# Pi5_Power.net
KiCad netlist of a schematic drawn in Altium Designer
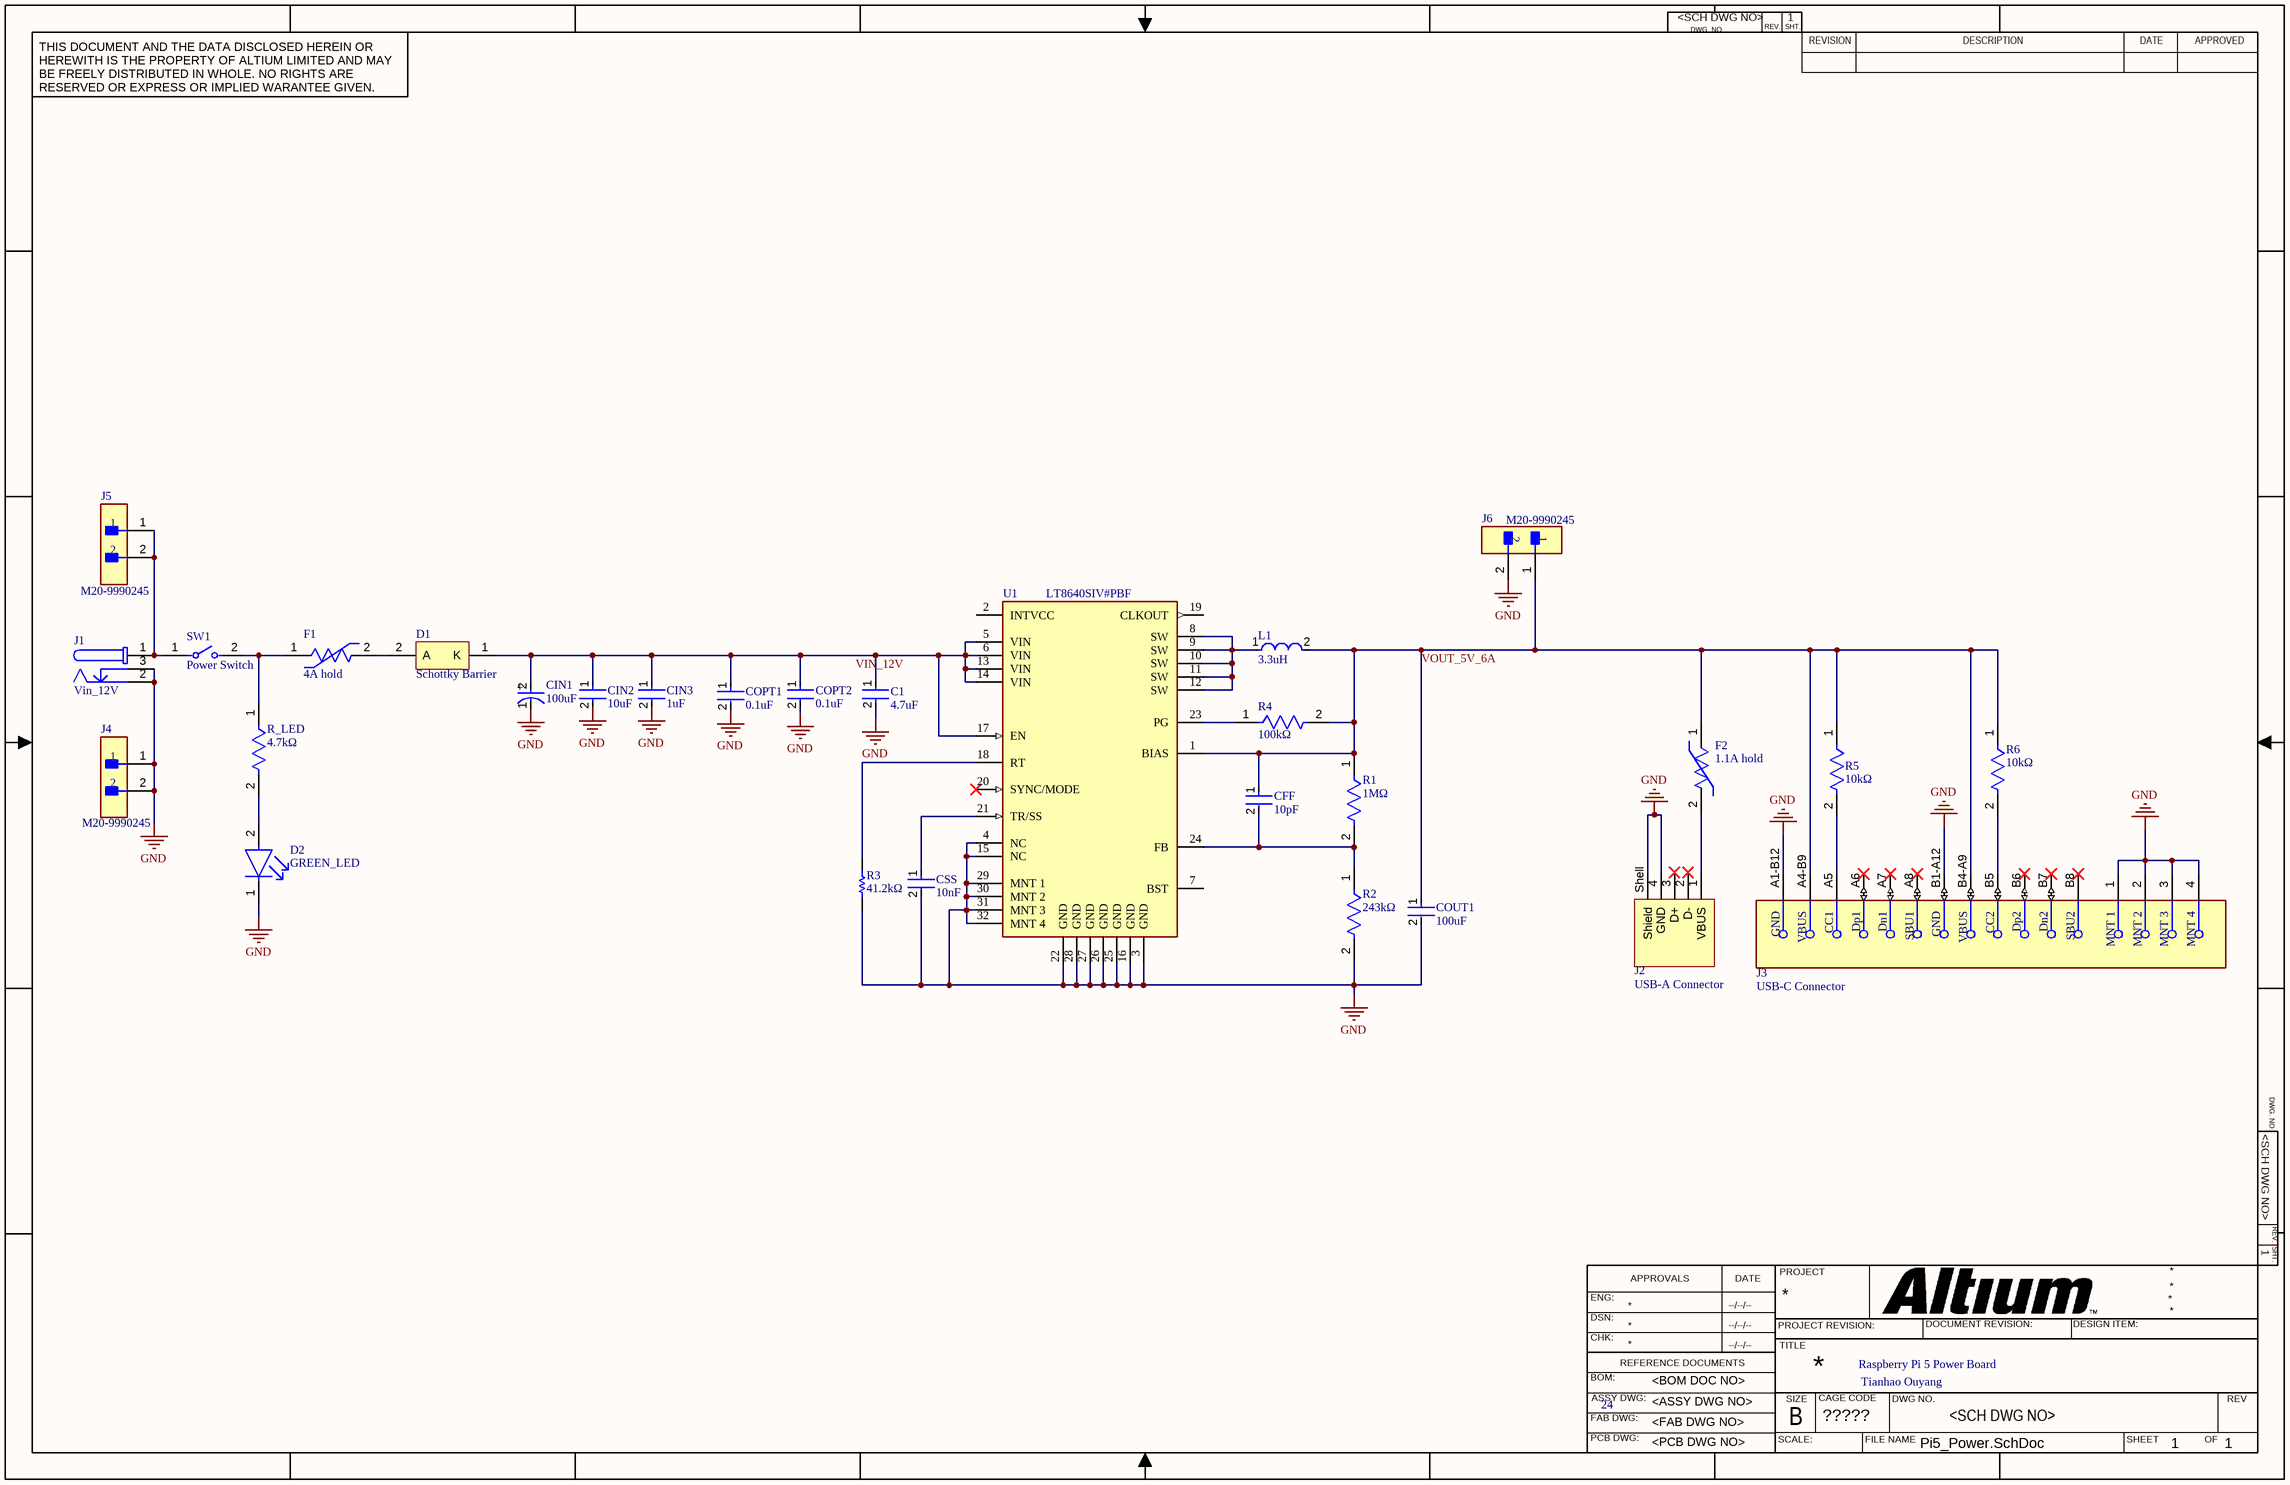
[diagram p0: Pi5_Power.SchDoc]

(export (version "E")
  (design (tool "Eeschema 10.0.6"))
  (components
    (comp (ref "C1")
      (value "4.7uF")
      (footprint "FP-GCM32E-0_3-IPC_B")
      (description "Ceramic Capacitor for Automotive 4.7uF ±10% 50VDC X7R 1210 Embossed T/R")
      (fields (field (name "VOLTAGE") "50V") (field (name "TOLERANCE") "20%"))
      (libsource (lib "Altium Content Vault") (part "f23184f103b6ebe33a8c269c53dcba6"))
    )
    (comp (ref "CFF")
      (value "10pF")
      (footprint "FP-C0805C-DN-MFG")
      (description "C0805 10 pF C0G 30ppm/°C 5.00% 250 V")
      (fields (field (name "TOLERANCE") "0.05") (field (name "MANUFACTURER PART NUMBER") "C0805C100JAGACTU"))
      (libsource (lib "Altium Content Vault") (part "b4654b650e69147ec39a6b967a45e02"))
    )
    (comp (ref "CIN1")
      (value "100uF")
      (footprint "FP-RAD-TH-D_6_3_0_5-L_11-MFG")
      (description "Aluminum Electrolytic Capacitors (Radial Lead Type) 100uF ±20% 25V")
      (fields (field (name "TOLERANCE") "20%"))
      (libsource (lib "Altium Content Vault") (part "a00bbbee19879c290e62620ae7e47b1"))
    )
    (comp (ref "CIN2")
      (value "10uF")
      (footprint "FP-GRM32-MFG")
      (description "CAP CER 10UF 50V X7R 1210")
      (fields (field (name "TOLERANCE") "10%") (field (name "MANUFACTURER PART NUMBER") "GRM32ER71H106KA12L"))
      (libsource (lib "Altium Content Vault") (part "11868f565c42a9108669ba33697ecf6"))
    )
    (comp (ref "CIN3")
      (value "1uF")
      (footprint "FP-C3216-160-0_2-IPC_B")
      (description "Multilayer Ceramic Capacitors 1uF ±10% 50V X7R SMD 1206")
      (fields (field (name "VOLTAGE") "25V") (field (name "TOLERANCE") "10%"))
      (libsource (lib "Altium Content Vault") (part "11868f565c42a9108669ba33697ecf6"))
    )
    (comp (ref "COPT1")
      (value "0.1uF")
      (footprint "FP-C1206C-EB-MFG")
      (description "CAP CER 0.1UF 250V X7R 1206")
      (fields
        (field (name "MANUFACTURER PART NUMBER") "C1206C104JARACTU")
        (field (name "OCTOPART") "https://octopart.com/c1206c104jaractu-kemet-16430893")
      )
      (libsource (lib "Altium Content Vault") (part "b4654b650e69147ec39a6b967a45e02"))
    )
    (comp (ref "COPT2")
      (value "0.1uF")
      (footprint "FP-C1206C-EB-MFG")
      (description "CAP CER 0.1UF 250V X7R 1206")
      (fields
        (field (name "MANUFACTURER PART NUMBER") "C1206C104JARACTU")
        (field (name "OCTOPART") "https://octopart.com/c1206c104jaractu-kemet-16430893")
      )
      (libsource (lib "Altium Content Vault") (part "b4654b650e69147ec39a6b967a45e02"))
    )
    (comp (ref "COUT1")
      (value "100uF")
      (footprint "FP-GRM32E-0_3-0_2-IPC_B")
      (description "Chip Multilayer Ceramic Capacitors for General Purpose, 1210, 100uF, X5R, 15%, 20%, 10V")
      (fields (field (name "TOLERANCE") "20%"))
      (libsource (lib "Altium Content Vault") (part "02cd4be3c70576c341d710602a673aa"))
    )
    (comp (ref "CSS")
      (value "10nF")
      (footprint "FP-C0603C-CF-MFG")
      (description "C0603 10,000 pF X7R 30ppm/°C 10.00% 25 V")
      (fields (field (name "TOLERANCE") "0.1") (field (name "MANUFACTURER PART NUMBER") "C0603C103K3RAC7411"))
      (libsource (lib "Altium Content Vault") (part "b4654b650e69147ec39a6b967a45e02"))
    )
    (comp (ref "D1")
      (value "Schottky Barrier")
      (footprint "ONSC-SMC-2-403-03_V")
      (description "Schottky Power Rectifier, 2-Pin SMC, Pb-Free, Tape and Reel")
      (fields (field (name "MANUFACTURER") "On Semiconductor") (field (name "PARTNUMBER") "MBRS540T3G"))
      (libsource (lib "Altium Content Vault") (part "ONSC-D-K1A2-2_A"))
    )
    (comp (ref "D2")
      (value "GREEN_LED")
      (footprint "FP-APHD1608LZGCK-MFG")
      (description "LED GREEN CLEAR 1608 SMD")
      (libsource (lib "Altium Content Vault") (part "8706943c75ba83719d021d2fdc84c58"))
    )
    (comp (ref "F1")
      (value "4A hold")
      (footprint "FP-2920L400-15MR-MFG")
      (description "PTC RESET FUSE 15V 4A 2920")
      (libsource (lib "Altium Content Vault") (part "fc31388045fc42ab786d6d00b506e9f"))
    )
    (comp (ref "F2")
      (value "1.1A hold")
      (footprint "FP-NANOSMDC110F-2-MFG")
      (description "PTC RESET FUSE 6V 1.1A 1206")
      (fields
        (field (name "MANUFACTURER") "Littelfuse")
        (field (name "OCTOPART") "https://octopart.com/nanosmdc110f-2-littelfuse-74215055")
      )
      (libsource (lib "Altium Content Vault") (part "fdf083d5f6389a9a1c4e51137f46658"))
    )
    (comp (ref "J1")
      (value "Vin_12V")
      (footprint "694108301002")
      (description "DC Power Jack Connector WR-DC, Male, Right Angled, THT, 5 A, 24 V")
      (libsource (lib "Altium Content Vault") (part "DC Power Jack"))
    )
    (comp (ref "J2")
      (value "USB-A Connector")
      (footprint "62900416021")
      (description "Wr-com; Right Angle Version 2.0; Connector SMT Socket, 30 V AC, 1.5A, 62900")
      (libsource (lib "Altium Content Vault") (part "USB 2.0_Type A_Receptacle_1 Port"))
    )
    (comp (ref "J3")
      (value "USB-C Connector")
      (footprint "FP-USB4105-GF-A-MFG")
      (description "CONN RCPT USB2.0 TYPEC 5A")
      (fields (field (name "MANUFACTURER PART NUMBER") "USB4105-GF-A") (field (name "MANUFACTURER") "GCT"))
      (libsource (lib "Altium Content Vault") (part "e7c17a616881a82b79941196b4bec10"))
    )
    (comp (ref "J4")
      (value "M20-9990245")
      (footprint "FP-M20-9990245-MFG")
      (description "CONN HEADER VERT 2POS 2.54MM")
      (fields (field (name "VOLTAGE") "50V"))
      (libsource (lib "") (part "3bc925449376181038e59eaffc5286c_1"))
    )
    (comp (ref "J5")
      (value "M20-9990245")
      (footprint "FP-M20-9990245-MFG")
      (description "CONN HEADER VERT 2POS 2.54MM")
      (fields (field (name "VOLTAGE") "50V"))
      (libsource (lib "") (part "3bc925449376181038e59eaffc5286c_1"))
    )
    (comp (ref "J6")
      (value "M20-9990245")
      (footprint "FP-M20-9990245-MFG")
      (description "CONN HEADER VERT 2POS 2.54MM")
      (fields (field (name "VOLTAGE") "50V"))
      (libsource (lib "Altium Content Vault") (part "3bc925449376181038e59eaffc5286c"))
    )
    (comp (ref "L1")
      (value "3.3uH")
      (footprint "FP-IHLP-3232DZ-FP_2_413x5-MFG")
      (description "Commercial Inductors, Low DCR Series 3.3uH 10.5A 14.9mΩ 20%")
      (fields (field (name "TOLERANCE") "20%"))
      (libsource (lib "Altium Content Vault") (part "725321dda6339637d4d059423bc1c3c"))
    )
    (comp (ref "R1")
      (value "1MΩ")
      (footprint "FP-RMCF0603-IPC_B")
      (description "1MΩ ±1% 0.1W 0603 Thick Film Chip Resistor AEC-Q200 compliant")
      (fields (field (name "TOLERANCE") "1%"))
      (libsource (lib "Altium Content Vault") (part "1029c3af85768c4190bb7ad29bc67b5"))
    )
    (comp (ref "R2")
      (value "243kΩ")
      (footprint "FP-RMCF0603-IPC_A")
      (description "243kΩ ±1% 0.1W 0603 Thick Film Chip Resistor AEC-Q200 compliant")
      (fields (field (name "TOLERANCE") "1%"))
      (libsource (lib "Altium Content Vault") (part "1029c3af85768c4190bb7ad29bc67b5"))
    )
    (comp (ref "R3")
      (value "41.2kΩ")
      (footprint "RESC1608X55X30ML20T10")
      (fields (field (name "PART NUMBER") "RK73H1JTTD4122F") (field (name "MANUFACTURER") "KOA Speer"))
      (libsource (lib "Altium Content Vault") (part "RES"))
    )
    (comp (ref "R4")
      (value "100kΩ")
      (footprint "FP-CRGP0603-IPC_C")
      (description "CRGP 0603 100K 1%")
      (fields
        (field (name "MANUFACTURER") "TE")
        (field (name "OCTOPART") "https://octopart.com/crgp0603f100k-te+connectivity-91018719")
      )
      (libsource (lib "Altium Content Vault") (part "1029c3af85768c4190bb7ad29bc67b5"))
    )
    (comp (ref "R5")
      (value "10kΩ")
      (footprint "FP-RC0603-0_55-IPC_C")
      (description "RES 10K OHM 1% 1/10W 0603")
      (fields (field (name "TOLERANCE") "1%"))
      (libsource (lib "Altium Content Vault") (part "1029c3af85768c4190bb7ad29bc67b5"))
    )
    (comp (ref "R6")
      (value "10kΩ")
      (footprint "FP-RC0603-0_55-IPC_C")
      (description "RES 10K OHM 1% 1/10W 0603")
      (fields (field (name "TOLERANCE") "1%"))
      (libsource (lib "Altium Content Vault") (part "1029c3af85768c4190bb7ad29bc67b5"))
    )
    (comp (ref "R_LED")
      (value "4.7kΩ")
      (footprint "FP-MCT0603-IPC_C")
      (description "RES SMD 100 OHM 1% 1/8W 0603")
      (fields (field (name "TOLERANCE") "0.1%"))
      (libsource (lib "Altium Content Vault") (part "1029c3af85768c4190bb7ad29bc67b5"))
    )
    (comp (ref "SW1")
      (value "Power Switch")
      (footprint "FP-L101011MS02Q-MFG")
      (description "SWITCH SLIDE SPST 4A 125V")
      (libsource (lib "Altium Content Vault") (part "bb27bde45df87f1f469753f287ef5ae"))
    )
    (comp (ref "U1")
      (value "LT8640SIV#PBF")
      (footprint "FP-LQFN-24-05-08-1511-MFG")
      (description "IC REG BUCK ADJUSTABLE 6A 24LQFN")
      (libsource (lib "Altium Content Vault") (part "91d9de4f4c7515ea037f48a7b82e954"))
    )
  )
  (nets
    (net (code "1") (name "/VIN_12V") (class "Default")
      (node (ref "C1") (pin "1") (pinfunction "1_1") (pintype "passive"))
      (node (ref "CIN1") (pin "2") (pinfunction "A_2") (pintype "passive"))
      (node (ref "CIN2") (pin "1") (pinfunction "1_1") (pintype "passive"))
      (node (ref "CIN3") (pin "1") (pinfunction "1_1") (pintype "passive"))
      (node (ref "COPT1") (pin "1") (pinfunction "1_1") (pintype "passive"))
      (node (ref "COPT2") (pin "1") (pinfunction "1_1") (pintype "passive"))
      (node (ref "D1") (pin "1") (pinfunction "K_1") (pintype "passive"))
      (node (ref "U1") (pin "13") (pinfunction "VIN_13") (pintype "power_in"))
      (node (ref "U1") (pin "14") (pinfunction "VIN_14") (pintype "power_in"))
      (node (ref "U1") (pin "17") (pinfunction "EN_17") (pintype "input"))
      (node (ref "U1") (pin "5") (pinfunction "VIN_5") (pintype "power_in"))
      (node (ref "U1") (pin "6") (pinfunction "VIN_6") (pintype "power_in"))
    )
    (net (code "2") (name "/VOUT_5V_6A") (class "Default")
      (node (ref "CFF") (pin "1") (pinfunction "1_1") (pintype "passive"))
      (node (ref "COUT1") (pin "1") (pinfunction "1_1") (pintype "passive"))
      (node (ref "F2") (pin "1") (pinfunction "1_1") (pintype "passive"))
      (node (ref "J3") (pin "A4-B9") (pinfunction "VBUS_A4-B9") (pintype "power_in"))
      (node (ref "J3") (pin "B4-A9") (pinfunction "VBUS_B4-A9") (pintype "bidirectional"))
      (node (ref "J6") (pin "1") (pinfunction "1_1") (pintype "passive"))
      (node (ref "L1") (pin "2") (pinfunction "2_2") (pintype "passive"))
      (node (ref "R1") (pin "1") (pinfunction "1_1") (pintype "passive"))
      (node (ref "R4") (pin "2") (pinfunction "2_2") (pintype "passive"))
      (node (ref "R5") (pin "1") (pinfunction "1_1") (pintype "passive"))
      (node (ref "R6") (pin "1") (pinfunction "1_1") (pintype "passive"))
      (node (ref "U1") (pin "1") (pinfunction "BIAS_1") (pintype "passive"))
    )
    (net (code "3") (name "GND") (class "Default")
      (node (ref "C1") (pin "2") (pinfunction "2_2") (pintype "passive"))
      (node (ref "CIN1") (pin "1") (pinfunction "C_1") (pintype "passive"))
      (node (ref "CIN2") (pin "2") (pinfunction "2_2") (pintype "passive"))
      (node (ref "CIN3") (pin "2") (pinfunction "2_2") (pintype "passive"))
      (node (ref "COPT1") (pin "2") (pinfunction "2_2") (pintype "passive"))
      (node (ref "COPT2") (pin "2") (pinfunction "2_2") (pintype "passive"))
      (node (ref "COUT1") (pin "2") (pinfunction "2_2") (pintype "passive"))
      (node (ref "CSS") (pin "2") (pinfunction "2_2") (pintype "passive"))
      (node (ref "D2") (pin "1") (pinfunction "C_1") (pintype "passive"))
      (node (ref "J1") (pin "2") (pinfunction "2_2") (pintype "passive"))
      (node (ref "J1") (pin "3") (pinfunction "3_3") (pintype "passive"))
      (node (ref "J2") (pin "4") (pinfunction "GND_4") (pintype "passive"))
      (node (ref "J2") (pin "Shell") (pinfunction "Shield_Shell") (pintype "passive"))
      (node (ref "J3") (pin "1") (pinfunction "MNT_1_1") (pintype "power_in"))
      (node (ref "J3") (pin "2") (pinfunction "MNT_2_2") (pintype "power_in"))
      (node (ref "J3") (pin "3") (pinfunction "MNT_3_3") (pintype "power_in"))
      (node (ref "J3") (pin "4") (pinfunction "MNT_4_4") (pintype "power_in"))
      (node (ref "J3") (pin "A1-B12") (pinfunction "GND_A1-B12") (pintype "power_in"))
      (node (ref "J3") (pin "B1-A12") (pinfunction "GND_B1-A12") (pintype "bidirectional"))
      (node (ref "J4") (pin "1") (pinfunction "1_1") (pintype "passive"))
      (node (ref "J4") (pin "2") (pinfunction "2_2") (pintype "passive"))
      (node (ref "J6") (pin "2") (pinfunction "2_2") (pintype "passive"))
      (node (ref "R2") (pin "2") (pinfunction "2_2") (pintype "passive"))
      (node (ref "R3") (pin "1") (pinfunction "1_1") (pintype "passive"))
      (node (ref "U1") (pin "15") (pinfunction "NC_15") (pintype "passive"))
      (node (ref "U1") (pin "16") (pinfunction "GND_16") (pintype "power_in"))
      (node (ref "U1") (pin "22") (pinfunction "GND_22") (pintype "power_in"))
      (node (ref "U1") (pin "25") (pinfunction "GND_25") (pintype "power_in"))
      (node (ref "U1") (pin "26") (pinfunction "GND_26") (pintype "power_in"))
      (node (ref "U1") (pin "27") (pinfunction "GND_27") (pintype "power_in"))
      (node (ref "U1") (pin "28") (pinfunction "GND_28") (pintype "power_in"))
      (node (ref "U1") (pin "29") (pinfunction "MNT_1_29") (pintype "passive"))
      (node (ref "U1") (pin "3") (pinfunction "GND_3") (pintype "power_in"))
      (node (ref "U1") (pin "30") (pinfunction "MNT_2_30") (pintype "passive"))
      (node (ref "U1") (pin "31") (pinfunction "MNT_3_31") (pintype "passive"))
      (node (ref "U1") (pin "32") (pinfunction "MNT_4_32") (pintype "passive"))
      (node (ref "U1") (pin "4") (pinfunction "NC_4") (pintype "passive"))
    )
    (net (code "4") (name "Net-(D1-A)") (class "Default")
      (node (ref "D1") (pin "2") (pinfunction "A_2") (pintype "passive"))
      (node (ref "F1") (pin "2") (pinfunction "2_2") (pintype "passive"))
    )
    (net (code "5") (name "Net-(D2-A)") (class "Default")
      (node (ref "D2") (pin "2") (pinfunction "A_2") (pintype "passive"))
      (node (ref "R_LED") (pin "2") (pinfunction "2_2") (pintype "passive"))
    )
    (net (code "6") (name "Net-(F1-Pad1)") (class "Default")
      (node (ref "F1") (pin "1") (pinfunction "1_1") (pintype "passive"))
      (node (ref "R_LED") (pin "1") (pinfunction "1_1") (pintype "passive"))
      (node (ref "SW1") (pin "2") (pinfunction "2_2") (pintype "passive"))
    )
    (net (code "7") (name "Net-(J1-Pad1)") (class "Default")
      (node (ref "J1") (pin "1") (pinfunction "1_1") (pintype "passive"))
      (node (ref "J5") (pin "1") (pinfunction "1_1") (pintype "passive"))
      (node (ref "J5") (pin "2") (pinfunction "2_2") (pintype "passive"))
      (node (ref "SW1") (pin "1") (pinfunction "1_1") (pintype "passive"))
    )
    (net (code "8") (name "Net-(J2-VBUS)") (class "Default")
      (node (ref "F2") (pin "2") (pinfunction "2_2") (pintype "passive"))
      (node (ref "J2") (pin "1") (pinfunction "VBUS_1") (pintype "passive"))
    )
    (net (code "9") (name "Net-(J3-CC1)") (class "Default")
      (node (ref "J3") (pin "A5") (pinfunction "CC1_A5") (pintype "power_in"))
      (node (ref "R5") (pin "2") (pinfunction "2_2") (pintype "passive"))
    )
    (net (code "10") (name "Net-(J3-CC2)") (class "Default")
      (node (ref "J3") (pin "B5") (pinfunction "CC2_B5") (pintype "bidirectional"))
      (node (ref "R6") (pin "2") (pinfunction "2_2") (pintype "passive"))
    )
    (net (code "11") (name "Net-(L1-Pad1)") (class "Default")
      (node (ref "L1") (pin "1") (pinfunction "1_1") (pintype "passive"))
      (node (ref "U1") (pin "10") (pinfunction "SW_10") (pintype "passive"))
      (node (ref "U1") (pin "11") (pinfunction "SW_11") (pintype "passive"))
      (node (ref "U1") (pin "12") (pinfunction "SW_12") (pintype "passive"))
      (node (ref "U1") (pin "8") (pinfunction "SW_8") (pintype "passive"))
      (node (ref "U1") (pin "9") (pinfunction "SW_9") (pintype "passive"))
    )
    (net (code "12") (name "Net-(U1-FB)") (class "Default")
      (node (ref "CFF") (pin "2") (pinfunction "2_2") (pintype "passive"))
      (node (ref "R1") (pin "2") (pinfunction "2_2") (pintype "passive"))
      (node (ref "R2") (pin "1") (pinfunction "1_1") (pintype "passive"))
      (node (ref "U1") (pin "24") (pinfunction "FB_24") (pintype "passive"))
    )
    (net (code "13") (name "Net-(U1-PG)") (class "Default")
      (node (ref "R4") (pin "1") (pinfunction "1_1") (pintype "passive"))
      (node (ref "U1") (pin "23") (pinfunction "PG_23") (pintype "open_collector"))
    )
    (net (code "14") (name "Net-(U1-RT)") (class "Default")
      (node (ref "R3") (pin "2") (pinfunction "2_2") (pintype "passive"))
      (node (ref "U1") (pin "18") (pinfunction "RT_18") (pintype "passive"))
    )
    (net (code "15") (name "Net-(U1-TR{slash}SS)") (class "Default")
      (node (ref "CSS") (pin "1") (pinfunction "1_1") (pintype "passive"))
      (node (ref "U1") (pin "21") (pinfunction "TR/SS_21") (pintype "input"))
    )
    (net (code "16") (name "unconnected-(J2-D+-Pad3)") (class "Default")
      (node (ref "J2") (pin "3") (pinfunction "D+_3") (pintype "passive+no_connect"))
    )
    (net (code "17") (name "unconnected-(J2-D--Pad2)") (class "Default")
      (node (ref "J2") (pin "2") (pinfunction "D-_2") (pintype "passive+no_connect"))
    )
    (net (code "18") (name "unconnected-(J3-Dn1-PadA7)") (class "Default")
      (node (ref "J3") (pin "A7") (pinfunction "Dn1_A7") (pintype "bidirectional+no_connect"))
    )
    (net (code "19") (name "unconnected-(J3-Dn2-PadB7)") (class "Default")
      (node (ref "J3") (pin "B7") (pinfunction "Dn2_B7") (pintype "bidirectional+no_connect"))
    )
    (net (code "20") (name "unconnected-(J3-Dp1-PadA6)") (class "Default")
      (node (ref "J3") (pin "A6") (pinfunction "Dp1_A6") (pintype "bidirectional+no_connect"))
    )
    (net (code "21") (name "unconnected-(J3-Dp2-PadB6)") (class "Default")
      (node (ref "J3") (pin "B6") (pinfunction "Dp2_B6") (pintype "bidirectional+no_connect"))
    )
    (net (code "22") (name "unconnected-(J3-SBU1-PadA8)") (class "Default")
      (node (ref "J3") (pin "A8") (pinfunction "SBU1_A8") (pintype "bidirectional+no_connect"))
    )
    (net (code "23") (name "unconnected-(J3-SBU2-PadB8)") (class "Default")
      (node (ref "J3") (pin "B8") (pinfunction "SBU2_B8") (pintype "power_in+no_connect"))
    )
    (net (code "24") (name "unconnected-(U1-BST-Pad7)") (class "Default")
      (node (ref "U1") (pin "7") (pinfunction "BST_7") (pintype "power_in"))
    )
    (net (code "25") (name "unconnected-(U1-CLKOUT-Pad19)") (class "Default")
      (node (ref "U1") (pin "19") (pinfunction "CLKOUT_19") (pintype "output"))
    )
    (net (code "26") (name "unconnected-(U1-INTVCC-Pad2)") (class "Default")
      (node (ref "U1") (pin "2") (pinfunction "INTVCC_2") (pintype "power_in"))
    )
    (net (code "27") (name "unconnected-(U1-SYNC{slash}MODE-Pad20)") (class "Default")
      (node (ref "U1") (pin "20") (pinfunction "SYNC/MODE_20") (pintype "input+no_connect"))
    )
  )
)
